# board.net
KiCad netlist of a schematic drawn in EAGLE
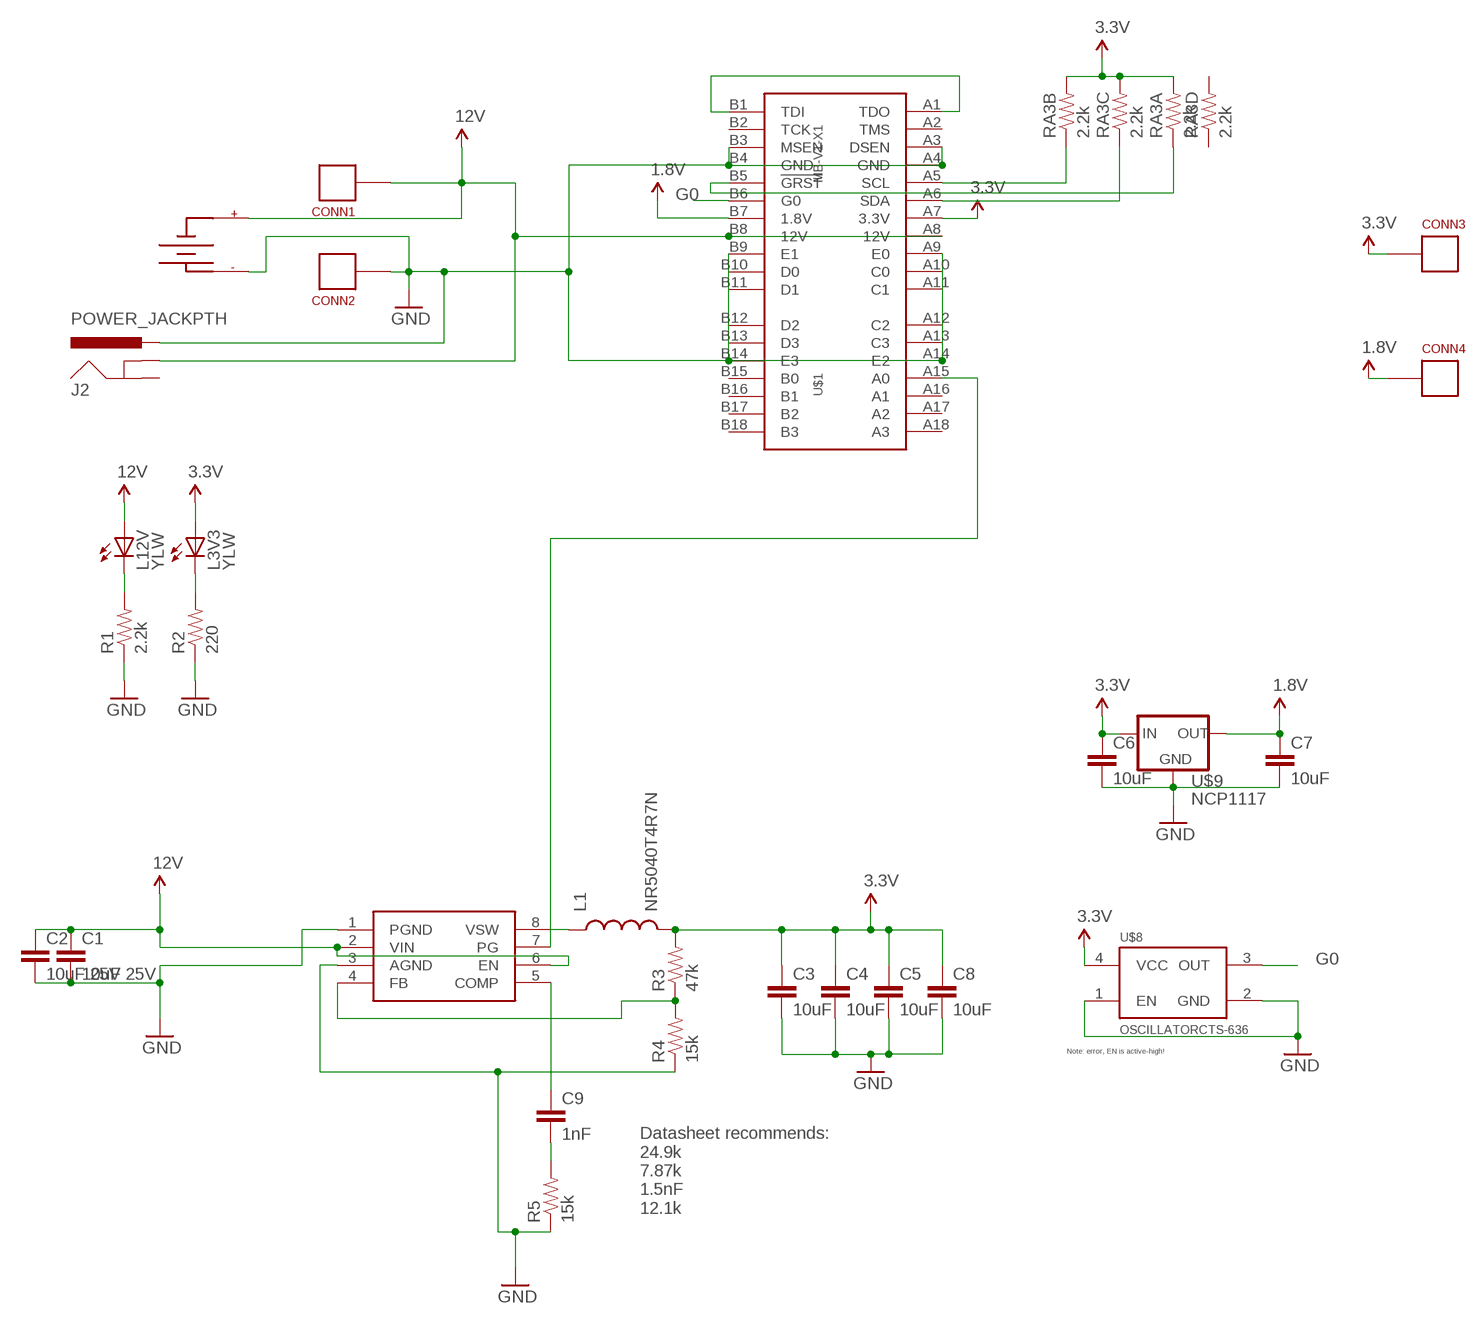
[diagram p0: schematic, sheet 1]

(export (version "E")
  (design (tool "Eeschema 10.0.6"))
  (components
    (comp (ref "C1")
      (value "10uF 25V")
      (footprint "eagle-import:0805")
      (libsource (lib "eagle-import") (part "CAP0805"))
    )
    (comp (ref "C2")
      (value "10uF 25V")
      (footprint "eagle-import:0805")
      (libsource (lib "eagle-import") (part "CAP0805"))
    )
    (comp (ref "C3")
      (value "10uF")
      (footprint "eagle-import:0805")
      (libsource (lib "eagle-import") (part "CAP0805"))
    )
    (comp (ref "C4")
      (value "10uF")
      (footprint "eagle-import:0805")
      (libsource (lib "eagle-import") (part "CAP0805"))
    )
    (comp (ref "C5")
      (value "10uF")
      (footprint "eagle-import:0805")
      (libsource (lib "eagle-import") (part "CAP0805"))
    )
    (comp (ref "C6")
      (value "10uF")
      (footprint "eagle-import:0805")
      (libsource (lib "eagle-import") (part "CAP0805"))
    )
    (comp (ref "C7")
      (value "10uF")
      (footprint "eagle-import:0805")
      (libsource (lib "eagle-import") (part "CAP0805"))
    )
    (comp (ref "C8")
      (value "10uF")
      (footprint "eagle-import:0805")
      (libsource (lib "eagle-import") (part "CAP0805"))
    )
    (comp (ref "C9")
      (value "1nF")
      (footprint "eagle-import:0402-CAP")
      (libsource (lib "eagle-import") (part "CAP0402-CAP"))
    )
    (comp (ref "CONN1")
      (value "CONNECTOR18AWG")
      (footprint "eagle-import:HOLE_18AWG")
      (libsource (lib "eagle-import") (part "CONNECTOR18AWG"))
    )
    (comp (ref "CONN2")
      (value "CONNECTOR18AWG")
      (footprint "eagle-import:HOLE_18AWG")
      (libsource (lib "eagle-import") (part "CONNECTOR18AWG"))
    )
    (comp (ref "CONN3")
      (value "CONNECTOR18AWG")
      (footprint "eagle-import:HOLE_18AWG")
      (libsource (lib "eagle-import") (part "CONNECTOR18AWG"))
    )
    (comp (ref "CONN4")
      (value "CONNECTOR18AWG")
      (footprint "eagle-import:HOLE_18AWG")
      (libsource (lib "eagle-import") (part "CONNECTOR18AWG"))
    )
    (comp (ref "J2")
      (value "POWER_JACKPTH")
      (footprint "eagle-import:POWER_JACK_PTH")
      (libsource (lib "eagle-import") (part "POWER_JACKPTH"))
    )
    (comp (ref "L1")
      (value "NR5040T4R7N")
      (footprint "eagle-import:NR5040")
      (libsource (lib "eagle-import") (part "INDUCTORNR5040"))
    )
    (comp (ref "L3V3")
      (value "YLW")
      (footprint "eagle-import:0603_LED")
      (libsource (lib "eagle-import") (part "LED0603"))
    )
    (comp (ref "L12V")
      (value "YLW")
      (footprint "eagle-import:0603_LED")
      (libsource (lib "eagle-import") (part "LED0603"))
    )
    (comp (ref "R1")
      (value "2.2k")
      (footprint "eagle-import:0603-RES")
      (libsource (lib "eagle-import") (part "RESISTOR0603"))
    )
    (comp (ref "R2")
      (value "220")
      (footprint "eagle-import:0603-RES")
      (libsource (lib "eagle-import") (part "RESISTOR0603"))
    )
    (comp (ref "R3")
      (value "47k")
      (footprint "eagle-import:0603-RES")
      (libsource (lib "eagle-import") (part "RESISTOR0603"))
    )
    (comp (ref "R4")
      (value "15k")
      (footprint "eagle-import:0603-RES")
      (libsource (lib "eagle-import") (part "RESISTOR0603"))
    )
    (comp (ref "R5")
      (value "15k")
      (footprint "eagle-import:0603-RES")
      (libsource (lib "eagle-import") (part "RESISTOR0603"))
    )
    (comp (ref "RA3")
      (value "2.2k")
      (footprint "eagle-import:0603-ARV")
      (libsource (lib "eagle-import") (part "RESISTOR_ARRAY0603_X4"))
    )
    (comp (ref "U$1")
      (value "MB-V1-X1")
      (footprint "eagle-import:PCIE-X1-EDGE")
      (libsource (lib "eagle-import") (part "MB-V1-X1"))
    )
    (comp (ref "U$4")
      (value "SUPPLYPCIE-6-RA")
      (footprint "eagle-import:MOLEX_MINIFITJR_6_RA")
      (libsource (lib "eagle-import") (part "SUPPLYPCIE-6-RA"))
    )
    (comp (ref "U$7")
      (value "NCP3170")
      (footprint "eagle-import:SO08")
      (libsource (lib "eagle-import") (part "NCP3170"))
    )
    (comp (ref "U$8")
      (value "OSCILLATORCTS-636")
      (footprint "eagle-import:CTS-636")
      (libsource (lib "eagle-import") (part "OSCILLATORCTS-636"))
    )
    (comp (ref "U$9")
      (value "NCP1117")
      (footprint "eagle-import:SOT223")
      (libsource (lib "eagle-import") (part "VREGSOT223"))
    )
  )
  (nets
    (net (code "1") (name "/G0") (class "Default")
      (node (ref "U$1") (pin "B6") (pinfunction "G0_B6") (pintype "bidirectional"))
      (node (ref "U$8") (pin "3") (pinfunction "OUT_3") (pintype "bidirectional"))
    )
    (net (code "2") (name "1.8V") (class "Default")
      (node (ref "C7") (pin "1") (pinfunction "1_1") (pintype "passive"))
      (node (ref "CONN4") (pin "P$1") (pinfunction "P_P$1") (pintype "bidirectional"))
      (node (ref "U$1") (pin "B7") (pinfunction "1.8V_B7") (pintype "bidirectional"))
      (node (ref "U$9") (pin "2") (pinfunction "OUT_2") (pintype "output"))
      (node (ref "U$9") (pin "4") (pinfunction "OUT_4") (pintype "output"))
    )
    (net (code "3") (name "3.3V") (class "Default")
      (node (ref "C3") (pin "1") (pinfunction "1_1") (pintype "passive"))
      (node (ref "C4") (pin "1") (pinfunction "1_1") (pintype "passive"))
      (node (ref "C5") (pin "1") (pinfunction "1_1") (pintype "passive"))
      (node (ref "C6") (pin "1") (pinfunction "1_1") (pintype "passive"))
      (node (ref "C8") (pin "1") (pinfunction "1_1") (pintype "passive"))
      (node (ref "CONN3") (pin "P$1") (pinfunction "P_P$1") (pintype "bidirectional"))
      (node (ref "L1") (pin "P$2") (pinfunction "2_P$2") (pintype "passive"))
      (node (ref "L3V3") (pin "A") (pinfunction "A_A") (pintype "passive"))
      (node (ref "R3") (pin "2") (pinfunction "2_2") (pintype "passive"))
      (node (ref "RA3") (pin "6") (pinfunction "2_6") (pintype "passive"))
      (node (ref "RA3") (pin "7") (pinfunction "2_7") (pintype "passive"))
      (node (ref "RA3") (pin "8") (pinfunction "2_8") (pintype "passive"))
      (node (ref "U$1") (pin "A7") (pinfunction "3.3V_A7") (pintype "bidirectional"))
      (node (ref "U$8") (pin "4") (pinfunction "VCC_4") (pintype "bidirectional"))
      (node (ref "U$9") (pin "3") (pinfunction "IN_3") (pintype "input"))
    )
    (net (code "4") (name "12V") (class "Default")
      (node (ref "C1") (pin "1") (pinfunction "1_1") (pintype "passive"))
      (node (ref "C2") (pin "1") (pinfunction "1_1") (pintype "passive"))
      (node (ref "CONN1") (pin "P$1") (pinfunction "P_P$1") (pintype "bidirectional"))
      (node (ref "J2") (pin "GNDBREAK") (pinfunction "GNDBREAK_GNDBREAK") (pintype "bidirectional"))
      (node (ref "L12V") (pin "A") (pinfunction "A_A") (pintype "passive"))
      (node (ref "U$1") (pin "A8") (pinfunction "12V_A8") (pintype "bidirectional"))
      (node (ref "U$1") (pin "B8") (pinfunction "12V_B8") (pintype "bidirectional"))
      (node (ref "U$4") (pin "1") (pinfunction "VSUPPLY_1") (pintype "bidirectional"))
      (node (ref "U$4") (pin "3") (pinfunction "VSUPPLY_3") (pintype "bidirectional"))
      (node (ref "U$7") (pin "2") (pinfunction "VIN_2") (pintype "bidirectional"))
      (node (ref "U$7") (pin "6") (pinfunction "EN_6") (pintype "bidirectional"))
    )
    (net (code "5") (name "GND") (class "Default")
      (node (ref "C1") (pin "2") (pinfunction "2_2") (pintype "passive"))
      (node (ref "C2") (pin "2") (pinfunction "2_2") (pintype "passive"))
      (node (ref "C3") (pin "2") (pinfunction "2_2") (pintype "passive"))
      (node (ref "C4") (pin "2") (pinfunction "2_2") (pintype "passive"))
      (node (ref "C5") (pin "2") (pinfunction "2_2") (pintype "passive"))
      (node (ref "C6") (pin "2") (pinfunction "2_2") (pintype "passive"))
      (node (ref "C7") (pin "2") (pinfunction "2_2") (pintype "passive"))
      (node (ref "C8") (pin "2") (pinfunction "2_2") (pintype "passive"))
      (node (ref "CONN2") (pin "P$1") (pinfunction "P_P$1") (pintype "bidirectional"))
      (node (ref "J2") (pin "PWR") (pinfunction "PWR_PWR") (pintype "bidirectional"))
      (node (ref "R1") (pin "1") (pinfunction "1_1") (pintype "passive"))
      (node (ref "R2") (pin "1") (pinfunction "1_1") (pintype "passive"))
      (node (ref "R4") (pin "1") (pinfunction "1_1") (pintype "passive"))
      (node (ref "R5") (pin "1") (pinfunction "1_1") (pintype "passive"))
      (node (ref "U$1") (pin "A14") (pinfunction "E2_A14") (pintype "bidirectional"))
      (node (ref "U$1") (pin "A3") (pinfunction "DSEN_A3") (pintype "bidirectional"))
      (node (ref "U$1") (pin "A4") (pinfunction "GND_A4") (pintype "bidirectional"))
      (node (ref "U$1") (pin "A9") (pinfunction "E0_A9") (pintype "bidirectional"))
      (node (ref "U$1") (pin "B14") (pinfunction "E3_B14") (pintype "bidirectional"))
      (node (ref "U$1") (pin "B3") (pinfunction "MSEN_B3") (pintype "bidirectional"))
      (node (ref "U$1") (pin "B4") (pinfunction "GND_B4") (pintype "bidirectional"))
      (node (ref "U$1") (pin "B9") (pinfunction "E1_B9") (pintype "bidirectional"))
      (node (ref "U$4") (pin "4") (pinfunction "GND_4") (pintype "bidirectional"))
      (node (ref "U$4") (pin "6") (pinfunction "GND_6") (pintype "bidirectional"))
      (node (ref "U$7") (pin "1") (pinfunction "PGND_1") (pintype "bidirectional"))
      (node (ref "U$7") (pin "3") (pinfunction "AGND_3") (pintype "bidirectional"))
      (node (ref "U$8") (pin "1") (pinfunction "EN_1") (pintype "bidirectional"))
      (node (ref "U$8") (pin "2") (pinfunction "GND_2") (pintype "bidirectional"))
      (node (ref "U$9") (pin "1") (pinfunction "GND_1") (pintype "input"))
    )
    (net (code "6") (name "Net-(C9-Pad2)") (class "Default")
      (node (ref "C9") (pin "2") (pinfunction "2_2") (pintype "passive"))
      (node (ref "R5") (pin "2") (pinfunction "2_2") (pintype "passive"))
    )
    (net (code "7") (name "Net-(L1-1)") (class "Default")
      (node (ref "L1") (pin "P$1") (pinfunction "1_P$1") (pintype "passive"))
      (node (ref "U$7") (pin "8") (pinfunction "VSW_8") (pintype "bidirectional"))
    )
    (net (code "8") (name "Net-(L3V3-PadC)") (class "Default")
      (node (ref "L3V3") (pin "C") (pinfunction "C_C") (pintype "passive"))
      (node (ref "R2") (pin "2") (pinfunction "2_2") (pintype "passive"))
    )
    (net (code "9") (name "Net-(L12V-PadC)") (class "Default")
      (node (ref "L12V") (pin "C") (pinfunction "C_C") (pintype "passive"))
      (node (ref "R1") (pin "2") (pinfunction "2_2") (pintype "passive"))
    )
    (net (code "10") (name "Net-(RA3B-1)") (class "Default")
      (node (ref "RA3") (pin "2") (pinfunction "1_2") (pintype "passive"))
      (node (ref "U$1") (pin "A5") (pinfunction "SCL_A5") (pintype "bidirectional"))
    )
    (net (code "11") (name "Net-(RA3C-1)") (class "Default")
      (node (ref "RA3") (pin "3") (pinfunction "1_3") (pintype "passive"))
      (node (ref "U$1") (pin "A6") (pinfunction "SDA_A6") (pintype "bidirectional"))
    )
    (net (code "12") (name "Net-(U$1-A0)") (class "Default")
      (node (ref "U$1") (pin "A15") (pinfunction "A0_A15") (pintype "bidirectional"))
      (node (ref "U$7") (pin "7") (pinfunction "PG_7") (pintype "bidirectional"))
    )
    (net (code "13") (name "Net-(U$1-TDI)") (class "Default")
      (node (ref "U$1") (pin "A1") (pinfunction "TDO_A1") (pintype "bidirectional"))
      (node (ref "U$1") (pin "B1") (pinfunction "TDI_B1") (pintype "bidirectional"))
    )
    (net (code "14") (name "Net-(U$1-~{GRST})") (class "Default")
      (node (ref "RA3") (pin "1") (pinfunction "1_1") (pintype "passive"))
      (node (ref "U$1") (pin "B5") (pinfunction "~{GRST}_B5") (pintype "bidirectional"))
    )
    (net (code "15") (name "Net-(U$7-COMP)") (class "Default")
      (node (ref "C9") (pin "1") (pinfunction "1_1") (pintype "passive"))
      (node (ref "U$7") (pin "5") (pinfunction "COMP_5") (pintype "bidirectional"))
    )
    (net (code "16") (name "Net-(U$7-FB)") (class "Default")
      (node (ref "R3") (pin "1") (pinfunction "1_1") (pintype "passive"))
      (node (ref "R4") (pin "2") (pinfunction "2_2") (pintype "passive"))
      (node (ref "U$7") (pin "4") (pinfunction "FB_4") (pintype "bidirectional"))
    )
    (net (code "17") (name "unconnected-(J2-PadGND)") (class "Default")
      (node (ref "J2") (pin "GND") (pinfunction "GND_GND") (pintype "bidirectional"))
    )
    (net (code "18") (name "unconnected-(RA3D-1-Pad4)") (class "Default")
      (node (ref "RA3") (pin "4") (pinfunction "1_4") (pintype "passive"))
    )
    (net (code "19") (name "unconnected-(RA3D-2-Pad5)") (class "Default")
      (node (ref "RA3") (pin "5") (pinfunction "2_5") (pintype "passive"))
    )
    (net (code "20") (name "unconnected-(U$1-A1-PadA16)") (class "Default")
      (node (ref "U$1") (pin "A16") (pinfunction "A1_A16") (pintype "bidirectional"))
    )
    (net (code "21") (name "unconnected-(U$1-A2-PadA17)") (class "Default")
      (node (ref "U$1") (pin "A17") (pinfunction "A2_A17") (pintype "bidirectional"))
    )
    (net (code "22") (name "unconnected-(U$1-A3-PadA18)") (class "Default")
      (node (ref "U$1") (pin "A18") (pinfunction "A3_A18") (pintype "bidirectional"))
    )
    (net (code "23") (name "unconnected-(U$1-B0-PadB15)") (class "Default")
      (node (ref "U$1") (pin "B15") (pinfunction "B0_B15") (pintype "bidirectional"))
    )
    (net (code "24") (name "unconnected-(U$1-B1-PadB16)") (class "Default")
      (node (ref "U$1") (pin "B16") (pinfunction "B1_B16") (pintype "bidirectional"))
    )
    (net (code "25") (name "unconnected-(U$1-B2-PadB17)") (class "Default")
      (node (ref "U$1") (pin "B17") (pinfunction "B2_B17") (pintype "bidirectional"))
    )
    (net (code "26") (name "unconnected-(U$1-B3-PadB18)") (class "Default")
      (node (ref "U$1") (pin "B18") (pinfunction "B3_B18") (pintype "bidirectional"))
    )
    (net (code "27") (name "unconnected-(U$1-C0-PadA10)") (class "Default")
      (node (ref "U$1") (pin "A10") (pinfunction "C0_A10") (pintype "bidirectional"))
    )
    (net (code "28") (name "unconnected-(U$1-C1-PadA11)") (class "Default")
      (node (ref "U$1") (pin "A11") (pinfunction "C1_A11") (pintype "bidirectional"))
    )
    (net (code "29") (name "unconnected-(U$1-C2-PadA12)") (class "Default")
      (node (ref "U$1") (pin "A12") (pinfunction "C2_A12") (pintype "bidirectional"))
    )
    (net (code "30") (name "unconnected-(U$1-C3-PadA13)") (class "Default")
      (node (ref "U$1") (pin "A13") (pinfunction "C3_A13") (pintype "bidirectional"))
    )
    (net (code "31") (name "unconnected-(U$1-D0-PadB10)") (class "Default")
      (node (ref "U$1") (pin "B10") (pinfunction "D0_B10") (pintype "bidirectional"))
    )
    (net (code "32") (name "unconnected-(U$1-D1-PadB11)") (class "Default")
      (node (ref "U$1") (pin "B11") (pinfunction "D1_B11") (pintype "bidirectional"))
    )
    (net (code "33") (name "unconnected-(U$1-D2-PadB12)") (class "Default")
      (node (ref "U$1") (pin "B12") (pinfunction "D2_B12") (pintype "bidirectional"))
    )
    (net (code "34") (name "unconnected-(U$1-D3-PadB13)") (class "Default")
      (node (ref "U$1") (pin "B13") (pinfunction "D3_B13") (pintype "bidirectional"))
    )
    (net (code "35") (name "unconnected-(U$1-TCK-PadB2)") (class "Default")
      (node (ref "U$1") (pin "B2") (pinfunction "TCK_B2") (pintype "bidirectional"))
    )
    (net (code "36") (name "unconnected-(U$1-TMS-PadA2)") (class "Default")
      (node (ref "U$1") (pin "A2") (pinfunction "TMS_A2") (pintype "bidirectional"))
    )
  )
)
